# STM32F030F4P6_dev_board.net
KiCad netlist of a schematic drawn in Altium Designer
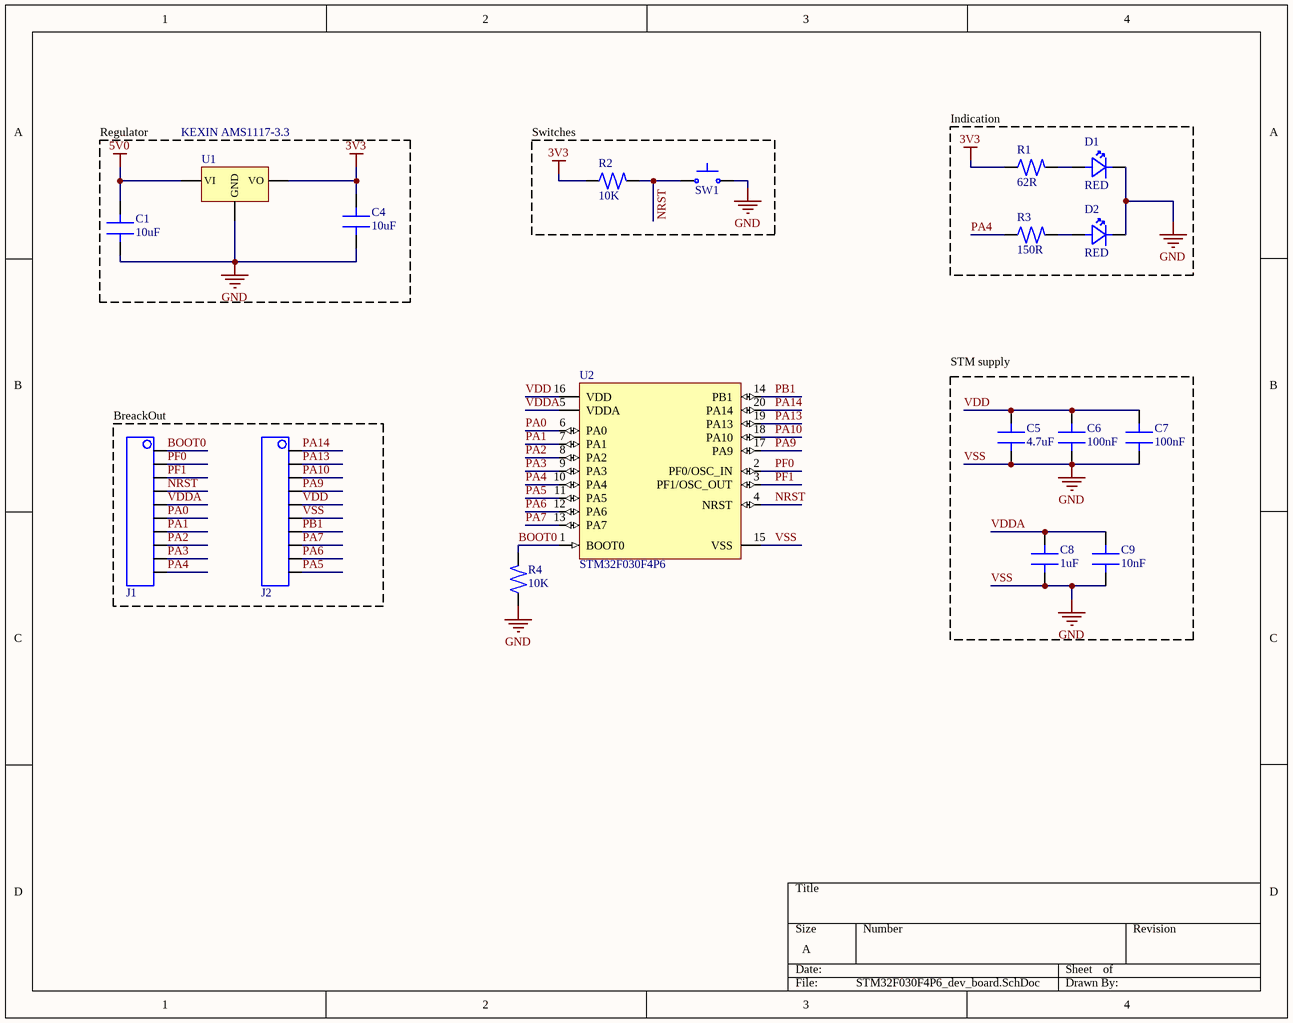
[diagram p0: STM32F030F4P6_dev_board.SchDoc]

(export (version "E")
  (design (tool "Eeschema 10.0.6"))
  (components
    (comp (ref "C1")
      (value "10uF")
      (footprint "Ceramic Capacitor 0603")
      (description "16V 10uF X5R ±20% 0603 Multilayer Ceramic Capacitors MLCC - SMD/SMT ROHS")
      (fields
        (field (name "MANUFACTURER") "YAGEO")
        (field (name "MANUFACTURER PART NUMBER") "CC0603MRX5R7BB106")
      )
      (libsource (lib "Symbols") (part "Ceramic Capacitor 0603 10uF"))
    )
    (comp (ref "C4")
      (value "10uF")
      (footprint "Ceramic Capacitor 0603")
      (description "16V 10uF X5R ±20% 0603 Multilayer Ceramic Capacitors MLCC - SMD/SMT ROHS")
      (fields
        (field (name "MANUFACTURER") "YAGEO")
        (field (name "MANUFACTURER PART NUMBER") "CC0603MRX5R7BB106")
      )
      (libsource (lib "Symbols") (part "Ceramic Capacitor 0603 10uF"))
    )
    (comp (ref "C5")
      (value "4.7uF")
      (footprint "Ceramic Capacitor 0603")
      (description "X7R 4.7nF 16V ±10% 0603 Multilayer Ceramic Capacitors MLCC - SMD/SMT ROHS")
      (fields
        (field (name "MANUFACTURER") "YAGEO")
        (field (name "MANUFACTURER PART NUMBER") "CC0603KRX7R7BB472")
      )
      (libsource (lib "Symbols") (part "Ceramic Capacitor 0603 4.7uF"))
    )
    (comp (ref "C6")
      (value "100nF")
      (footprint "Ceramic Capacitor 0603")
      (description "X7R 100nF 16V ±10% 0603 Multilayer Ceramic Capacitors MLCC - SMD/SMT ROHS")
      (fields
        (field (name "MANUFACTURER") "YAGEO")
        (field (name "MANUFACTURER PART NUMBER") "CC0603KRX7R7BB104")
      )
      (libsource (lib "Symbols") (part "Ceramic Capacitor 0603 100nF"))
    )
    (comp (ref "C7")
      (value "100nF")
      (footprint "Ceramic Capacitor 0603")
      (description "X7R 100nF 16V ±10% 0603 Multilayer Ceramic Capacitors MLCC - SMD/SMT ROHS")
      (fields
        (field (name "MANUFACTURER") "YAGEO")
        (field (name "MANUFACTURER PART NUMBER") "CC0603KRX7R7BB104")
      )
      (libsource (lib "Symbols") (part "Ceramic Capacitor 0603 100nF"))
    )
    (comp (ref "C8")
      (value "1uF")
      (footprint "Ceramic Capacitor 0603")
      (description "X7R 1uF 16V ±10% 0603 Multilayer Ceramic Capacitors MLCC - SMD/SMT ROHS")
      (fields
        (field (name "MANUFACTURER") "YAGEO")
        (field (name "MANUFACTURER PART NUMBER") "CC0603KRX7R7BB105")
      )
      (libsource (lib "Symbols") (part "Ceramic Capacitor 0603 1uF"))
    )
    (comp (ref "C9")
      (value "10nF")
      (footprint "Ceramic Capacitor 0603")
      (description "50V 10nF X7R ±10% 0603 Multilayer Ceramic Capacitors MLCC - SMD/SMT ROHS")
      (fields
        (field (name "MANUFACTURER") "YAGEO")
        (field (name "MANUFACTURER PART NUMBER") "CC0603KRX7R9BB103")
      )
      (libsource (lib "Symbols") (part "Ceramic Capacitor 0603 10nF"))
    )
    (comp (ref "D1")
      (value "RED")
      (footprint "LED 0805 SMD")
      (fields
        (field (name "MANUFACTURER") "Foshan NationStar Optoelectronics")
        (field (name "MANUFACTURER PART NUMBER") "NCD0805R1")
      )
      (libsource (lib "Symbols") (part "LED 0805 SMD"))
    )
    (comp (ref "D2")
      (value "RED")
      (footprint "LED 0805 SMD")
      (fields
        (field (name "MANUFACTURER") "Foshan NationStar Optoelectronics")
        (field (name "MANUFACTURER PART NUMBER") "NCD0805R1")
      )
      (libsource (lib "Symbols") (part "LED 0805 SMD"))
    )
    (comp (ref "J1")
      (value "Pin header 10pin")
      (footprint "Pin header 10pin")
      (fields
        (field (name "MANUFACTURER") "XKB Connectivity")
        (field (name "MANUFACTURER PART NUMBER") "X6511WV-10H-C60D30")
      )
      (libsource (lib "Symbols") (part "Pin header 10pin"))
    )
    (comp (ref "J2")
      (value "Pin header 10pin")
      (footprint "Pin header 10pin")
      (fields
        (field (name "MANUFACTURER") "XKB Connectivity")
        (field (name "MANUFACTURER PART NUMBER") "X6511WV-10H-C60D30")
      )
      (libsource (lib "Symbols") (part "Pin header 10pin"))
    )
    (comp (ref "R1")
      (value "62R")
      (footprint "Resistor 0603 SMD")
      (description "100mW Thick Film Resistors ±100ppm/℃ ±1% 62Ω 0603 Chip Resistor - Surface Mount ROHS")
      (fields
        (field (name "MANUFACTURER") "YAGEO")
        (field (name "MANUFACTURER PART NUMBER") "RC0603FR-0762RL")
      )
      (libsource (lib "Symbols") (part "Resistor 0603 62R SMD"))
    )
    (comp (ref "R2")
      (value "10K")
      (footprint "Resistor 0603 SMD")
      (description "100mW Thin Film Resistor ±25ppm/℃ ±0.1% 10kΩ 0603 Chip Resistor - Surface Mount ROHS")
      (fields
        (field (name "MANUFACTURER") "YAGEO")
        (field (name "MANUFACTURER PART NUMBER") "RT0603BRD0710KL")
      )
      (libsource (lib "Symbols") (part "Resistor 0603 10K SMD"))
    )
    (comp (ref "R3")
      (value "150R")
      (footprint "Resistor 0603 SMD")
      (description "100mW Thick Film Resistors ±100ppm/℃ ±1% 150Ω 0603 Chip Resistor - Surface Mount ROHS")
      (fields
        (field (name "MANUFACTURER") "YAGEO")
        (field (name "MANUFACTURER PART NUMBER") "RC0603FR-07150RL")
      )
      (libsource (lib "Symbols") (part "Resistor 0603 150R SMD"))
    )
    (comp (ref "R4")
      (value "10K")
      (footprint "Resistor 0603 SMD")
      (description "100mW Thin Film Resistor ±25ppm/℃ ±0.1% 10kΩ 0603 Chip Resistor - Surface Mount ROHS")
      (fields
        (field (name "MANUFACTURER") "YAGEO")
        (field (name "MANUFACTURER PART NUMBER") "RT0603BRD0710KL")
      )
      (libsource (lib "Symbols") (part "Resistor 0603 10K SMD"))
    )
    (comp (ref "SW1")
      (value "XKB Connectivity TS-1101-C-W")
      (footprint "XKB Connectivity TS-1101-C-W")
      (fields
        (field (name "MANUFACTURER") "XKB Connectivity")
        (field (name "MANUFACTURER PART NUMBER") "TS-1101-C-W")
      )
      (libsource (lib "Symbols") (part "XKB Connectivity TS-1101-C-W"))
    )
    (comp (ref "U1")
      (value "KEXIN AMS1117-3.3")
      (footprint "KEXIN AMS1117-3.3")
      (description "1A Fixed 3.3V Positive 18V SOT-223-4 Linear Voltage Regulators (LDO) ROHS")
      (fields (field (name "MANUFACTURER") "KENIX") (field (name "MANUFACTURER PART NUMBER") "AMS1117-3.3"))
      (libsource (lib "Symbols") (part "KEXIN AMS1117-3.3"))
    )
    (comp (ref "U2")
      (value "STM32F030F4P6")
      (footprint "STM32F030F4P6-TSSOP20")
      (fields (field (name "MANUFACTURER") "STMicroelectronics"))
      (libsource (lib "Symbols") (part "STM32F030F4P6"))
    )
  )
  (nets
    (net (code "1") (name "/BOOT0") (class "Default")
      (node (ref "J1") (pin "1") (pinfunction "1_1") (pintype "passive"))
      (node (ref "R4") (pin "2") (pinfunction "2_2") (pintype "passive"))
      (node (ref "U2") (pin "1") (pinfunction "BOOT0_1") (pintype "input"))
    )
    (net (code "2") (name "/NRST") (class "Default")
      (node (ref "J1") (pin "4") (pinfunction "4_4") (pintype "passive"))
      (node (ref "R2") (pin "2") (pinfunction "2_2") (pintype "passive"))
      (node (ref "SW1") (pin "1") (pinfunction "1_1") (pintype "passive"))
      (node (ref "U2") (pin "4") (pinfunction "NRST_4") (pintype "bidirectional"))
    )
    (net (code "3") (name "/PA0") (class "Default")
      (node (ref "J1") (pin "6") (pinfunction "6_6") (pintype "passive"))
      (node (ref "U2") (pin "6") (pinfunction "PA0_6") (pintype "bidirectional"))
    )
    (net (code "4") (name "/PA1") (class "Default")
      (node (ref "J1") (pin "7") (pinfunction "7_7") (pintype "passive"))
      (node (ref "U2") (pin "7") (pinfunction "PA1_7") (pintype "bidirectional"))
    )
    (net (code "5") (name "/PA2") (class "Default")
      (node (ref "J1") (pin "8") (pinfunction "8_8") (pintype "passive"))
      (node (ref "U2") (pin "8") (pinfunction "PA2_8") (pintype "bidirectional"))
    )
    (net (code "6") (name "/PA3") (class "Default")
      (node (ref "J1") (pin "9") (pinfunction "9_9") (pintype "passive"))
      (node (ref "U2") (pin "9") (pinfunction "PA3_9") (pintype "bidirectional"))
    )
    (net (code "7") (name "/PA4") (class "Default")
      (node (ref "J1") (pin "10") (pinfunction "10_10") (pintype "passive"))
      (node (ref "R3") (pin "1") (pinfunction "1_1") (pintype "passive"))
      (node (ref "U2") (pin "10") (pinfunction "PA4_10") (pintype "bidirectional"))
    )
    (net (code "8") (name "/PA5") (class "Default")
      (node (ref "J2") (pin "10") (pinfunction "10_10") (pintype "passive"))
      (node (ref "U2") (pin "11") (pinfunction "PA5_11") (pintype "bidirectional"))
    )
    (net (code "9") (name "/PA6") (class "Default")
      (node (ref "J2") (pin "9") (pinfunction "9_9") (pintype "passive"))
      (node (ref "U2") (pin "12") (pinfunction "PA6_12") (pintype "bidirectional"))
    )
    (net (code "10") (name "/PA7") (class "Default")
      (node (ref "J2") (pin "8") (pinfunction "8_8") (pintype "passive"))
      (node (ref "U2") (pin "13") (pinfunction "PA7_13") (pintype "bidirectional"))
    )
    (net (code "11") (name "/PA9") (class "Default")
      (node (ref "J2") (pin "4") (pinfunction "4_4") (pintype "passive"))
      (node (ref "U2") (pin "17") (pinfunction "PA9_17") (pintype "bidirectional"))
    )
    (net (code "12") (name "/PA10") (class "Default")
      (node (ref "J2") (pin "3") (pinfunction "3_3") (pintype "passive"))
      (node (ref "U2") (pin "18") (pinfunction "PA10_18") (pintype "bidirectional"))
    )
    (net (code "13") (name "/PA13") (class "Default")
      (node (ref "J2") (pin "2") (pinfunction "2_2") (pintype "passive"))
      (node (ref "U2") (pin "19") (pinfunction "PA13_19") (pintype "bidirectional"))
    )
    (net (code "14") (name "/PA14") (class "Default")
      (node (ref "J2") (pin "1") (pinfunction "1_1") (pintype "passive"))
      (node (ref "U2") (pin "20") (pinfunction "PA14_20") (pintype "bidirectional"))
    )
    (net (code "15") (name "/PB1") (class "Default")
      (node (ref "J2") (pin "7") (pinfunction "7_7") (pintype "passive"))
      (node (ref "U2") (pin "14") (pinfunction "PB1_14") (pintype "bidirectional"))
    )
    (net (code "16") (name "/PF0") (class "Default")
      (node (ref "J1") (pin "2") (pinfunction "2_2") (pintype "passive"))
      (node (ref "U2") (pin "2") (pinfunction "PF0/OSC_IN_2") (pintype "bidirectional"))
    )
    (net (code "17") (name "/PF1") (class "Default")
      (node (ref "J1") (pin "3") (pinfunction "3_3") (pintype "passive"))
      (node (ref "U2") (pin "3") (pinfunction "PF1/OSC_OUT_3") (pintype "bidirectional"))
    )
    (net (code "18") (name "/VDD") (class "Default")
      (node (ref "C5") (pin "1") (pinfunction "1_1") (pintype "passive"))
      (node (ref "C6") (pin "2") (pinfunction "2_2") (pintype "passive"))
      (node (ref "C7") (pin "2") (pinfunction "2_2") (pintype "passive"))
      (node (ref "J2") (pin "5") (pinfunction "5_5") (pintype "passive"))
      (node (ref "U2") (pin "16") (pinfunction "VDD_16") (pintype "power_in"))
    )
    (net (code "19") (name "/VDDA") (class "Default")
      (node (ref "C8") (pin "2") (pinfunction "2_2") (pintype "passive"))
      (node (ref "C9") (pin "1") (pinfunction "1_1") (pintype "passive"))
      (node (ref "J1") (pin "5") (pinfunction "5_5") (pintype "passive"))
      (node (ref "U2") (pin "5") (pinfunction "VDDA_5") (pintype "power_in"))
    )
    (net (code "20") (name "3V3") (class "Default")
      (node (ref "C4") (pin "2") (pinfunction "2_2") (pintype "passive"))
      (node (ref "R1") (pin "1") (pinfunction "1_1") (pintype "passive"))
      (node (ref "R2") (pin "1") (pinfunction "1_1") (pintype "passive"))
      (node (ref "U1") (pin "VO") (pinfunction "VO_VO") (pintype "passive"))
    )
    (net (code "21") (name "5V0") (class "Default")
      (node (ref "C1") (pin "2") (pinfunction "2_2") (pintype "passive"))
      (node (ref "U1") (pin "VI") (pinfunction "VI_VI") (pintype "passive"))
    )
    (net (code "22") (name "GND") (class "Default")
      (node (ref "C1") (pin "1") (pinfunction "1_1") (pintype "passive"))
      (node (ref "C4") (pin "1") (pinfunction "1_1") (pintype "passive"))
      (node (ref "C5") (pin "2") (pinfunction "2_2") (pintype "passive"))
      (node (ref "C6") (pin "1") (pinfunction "1_1") (pintype "passive"))
      (node (ref "C7") (pin "1") (pinfunction "1_1") (pintype "passive"))
      (node (ref "C8") (pin "1") (pinfunction "1_1") (pintype "passive"))
      (node (ref "C9") (pin "2") (pinfunction "2_2") (pintype "passive"))
      (node (ref "D1") (pin "C") (pinfunction "C_C") (pintype "passive"))
      (node (ref "D2") (pin "C") (pinfunction "C_C") (pintype "passive"))
      (node (ref "J2") (pin "6") (pinfunction "6_6") (pintype "passive"))
      (node (ref "R4") (pin "1") (pinfunction "1_1") (pintype "passive"))
      (node (ref "SW1") (pin "2") (pinfunction "2_2") (pintype "passive"))
      (node (ref "U1") (pin "GND") (pinfunction "GND_GND") (pintype "passive"))
      (node (ref "U2") (pin "15") (pinfunction "VSS_15") (pintype "power_in"))
    )
    (net (code "23") (name "Net-(D1-PadA)") (class "Default")
      (node (ref "D1") (pin "A") (pinfunction "A_A") (pintype "passive"))
      (node (ref "R1") (pin "2") (pinfunction "2_2") (pintype "passive"))
    )
    (net (code "24") (name "Net-(D2-PadA)") (class "Default")
      (node (ref "D2") (pin "A") (pinfunction "A_A") (pintype "passive"))
      (node (ref "R3") (pin "2") (pinfunction "2_2") (pintype "passive"))
    )
  )
)
